# adaptador_vga_scart.net
KiCad netlist of a schematic drawn in EAGLE
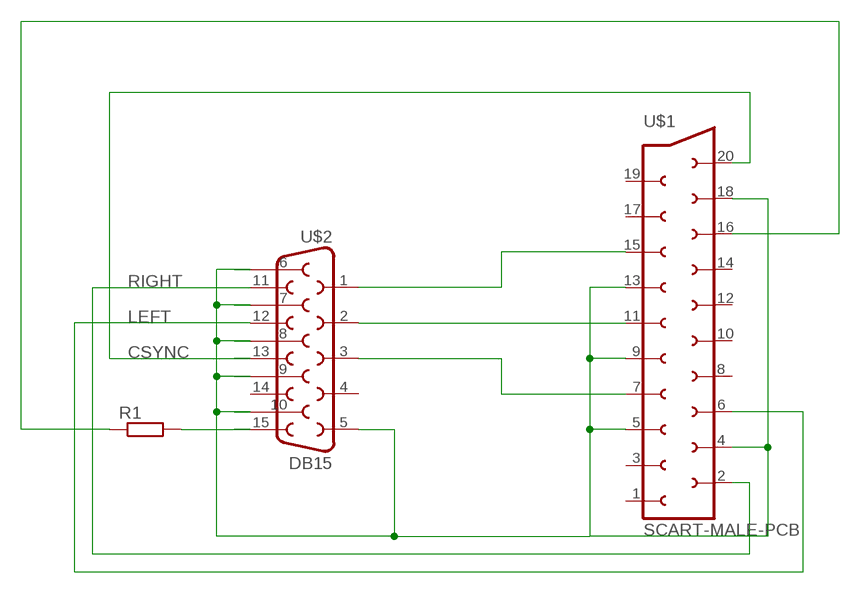
[diagram p0: schematic, sheet 1]

(export (version "E")
  (design (tool "Eeschema 10.0.6"))
  (components
    (comp (ref "R1")
      (value "R-EU_0204/7")
      (footprint "eagle-import:0204_7")
      (libsource (lib "eagle-import") (part "R-EU_0204/7"))
    )
    (comp (ref "U$1")
      (value "SCART-MALE-PCB")
      (footprint "eagle-import:SCART-PCB")
      (libsource (lib "eagle-import") (part "SCART-MALE-PCB"))
    )
    (comp (ref "U$2")
      (value "DB15")
      (footprint "eagle-import:DB15")
      (libsource (lib "eagle-import") (part "DB15"))
    )
  )
  (nets
    (net (code "1") (name "/CSYNC") (class "Default")
      (node (ref "U$1") (pin "20") (pinfunction "20_20") (pintype "passive"))
      (node (ref "U$2") (pin "13") (pinfunction "13_13") (pintype "passive"))
    )
    (net (code "2") (name "/GND") (class "Default")
      (node (ref "U$1") (pin "13") (pinfunction "13_13") (pintype "passive"))
      (node (ref "U$1") (pin "18") (pinfunction "18_18") (pintype "passive"))
      (node (ref "U$1") (pin "4") (pinfunction "4_4") (pintype "passive"))
      (node (ref "U$1") (pin "5") (pinfunction "5_5") (pintype "passive"))
      (node (ref "U$1") (pin "9") (pinfunction "9_9") (pintype "passive"))
      (node (ref "U$2") (pin "10") (pinfunction "10_10") (pintype "passive"))
      (node (ref "U$2") (pin "5") (pinfunction "5_5") (pintype "passive"))
      (node (ref "U$2") (pin "6") (pinfunction "6_6") (pintype "passive"))
      (node (ref "U$2") (pin "7") (pinfunction "7_7") (pintype "passive"))
      (node (ref "U$2") (pin "8") (pinfunction "8_8") (pintype "passive"))
      (node (ref "U$2") (pin "9") (pinfunction "9_9") (pintype "passive"))
    )
    (net (code "3") (name "/LEFT") (class "Default")
      (node (ref "U$1") (pin "6") (pinfunction "6_6") (pintype "passive"))
      (node (ref "U$2") (pin "12") (pinfunction "12_12") (pintype "passive"))
    )
    (net (code "4") (name "/RIGHT") (class "Default")
      (node (ref "U$1") (pin "2") (pinfunction "2_2") (pintype "passive"))
      (node (ref "U$2") (pin "11") (pinfunction "11_11") (pintype "passive"))
    )
    (net (code "5") (name "Net-(R1-Pad1)") (class "Default")
      (node (ref "R1") (pin "1") (pinfunction "1_1") (pintype "passive"))
      (node (ref "U$1") (pin "16") (pinfunction "16_16") (pintype "passive"))
    )
    (net (code "6") (name "Net-(R1-Pad2)") (class "Default")
      (node (ref "R1") (pin "2") (pinfunction "2_2") (pintype "passive"))
      (node (ref "U$2") (pin "15") (pinfunction "15_15") (pintype "passive"))
    )
    (net (code "7") (name "Net-(U$1-Pad7)") (class "Default")
      (node (ref "U$1") (pin "7") (pinfunction "7_7") (pintype "passive"))
      (node (ref "U$2") (pin "3") (pinfunction "3_3") (pintype "passive"))
    )
    (net (code "8") (name "Net-(U$1-Pad11)") (class "Default")
      (node (ref "U$1") (pin "11") (pinfunction "11_11") (pintype "passive"))
      (node (ref "U$2") (pin "2") (pinfunction "2_2") (pintype "passive"))
    )
    (net (code "9") (name "Net-(U$1-Pad15)") (class "Default")
      (node (ref "U$1") (pin "15") (pinfunction "15_15") (pintype "passive"))
      (node (ref "U$2") (pin "1") (pinfunction "1_1") (pintype "passive"))
    )
    (net (code "10") (name "unconnected-(U$1-Pad1)") (class "Default")
      (node (ref "U$1") (pin "1") (pinfunction "1_1") (pintype "passive"))
    )
    (net (code "11") (name "unconnected-(U$1-Pad3)") (class "Default")
      (node (ref "U$1") (pin "3") (pinfunction "3_3") (pintype "passive"))
    )
    (net (code "12") (name "unconnected-(U$1-Pad8)") (class "Default")
      (node (ref "U$1") (pin "8") (pinfunction "8_8") (pintype "passive"))
    )
    (net (code "13") (name "unconnected-(U$1-Pad10)") (class "Default")
      (node (ref "U$1") (pin "10") (pinfunction "10_10") (pintype "passive"))
    )
    (net (code "14") (name "unconnected-(U$1-Pad12)") (class "Default")
      (node (ref "U$1") (pin "12") (pinfunction "12_12") (pintype "passive"))
    )
    (net (code "15") (name "unconnected-(U$1-Pad14)") (class "Default")
      (node (ref "U$1") (pin "14") (pinfunction "14_14") (pintype "passive"))
    )
    (net (code "16") (name "unconnected-(U$1-Pad17)") (class "Default")
      (node (ref "U$1") (pin "17") (pinfunction "17_17") (pintype "passive"))
    )
    (net (code "17") (name "unconnected-(U$1-Pad19)") (class "Default")
      (node (ref "U$1") (pin "19") (pinfunction "19_19") (pintype "passive"))
    )
    (net (code "18") (name "unconnected-(U$2-Pad4)") (class "Default")
      (node (ref "U$2") (pin "4") (pinfunction "4_4") (pintype "passive"))
    )
    (net (code "19") (name "unconnected-(U$2-Pad14)") (class "Default")
      (node (ref "U$2") (pin "14") (pinfunction "14_14") (pintype "passive"))
    )
  )
)
